# LPCB218_-_RS485_MUX_CONTROL.net
KiCad netlist of a schematic drawn in Altium Designer
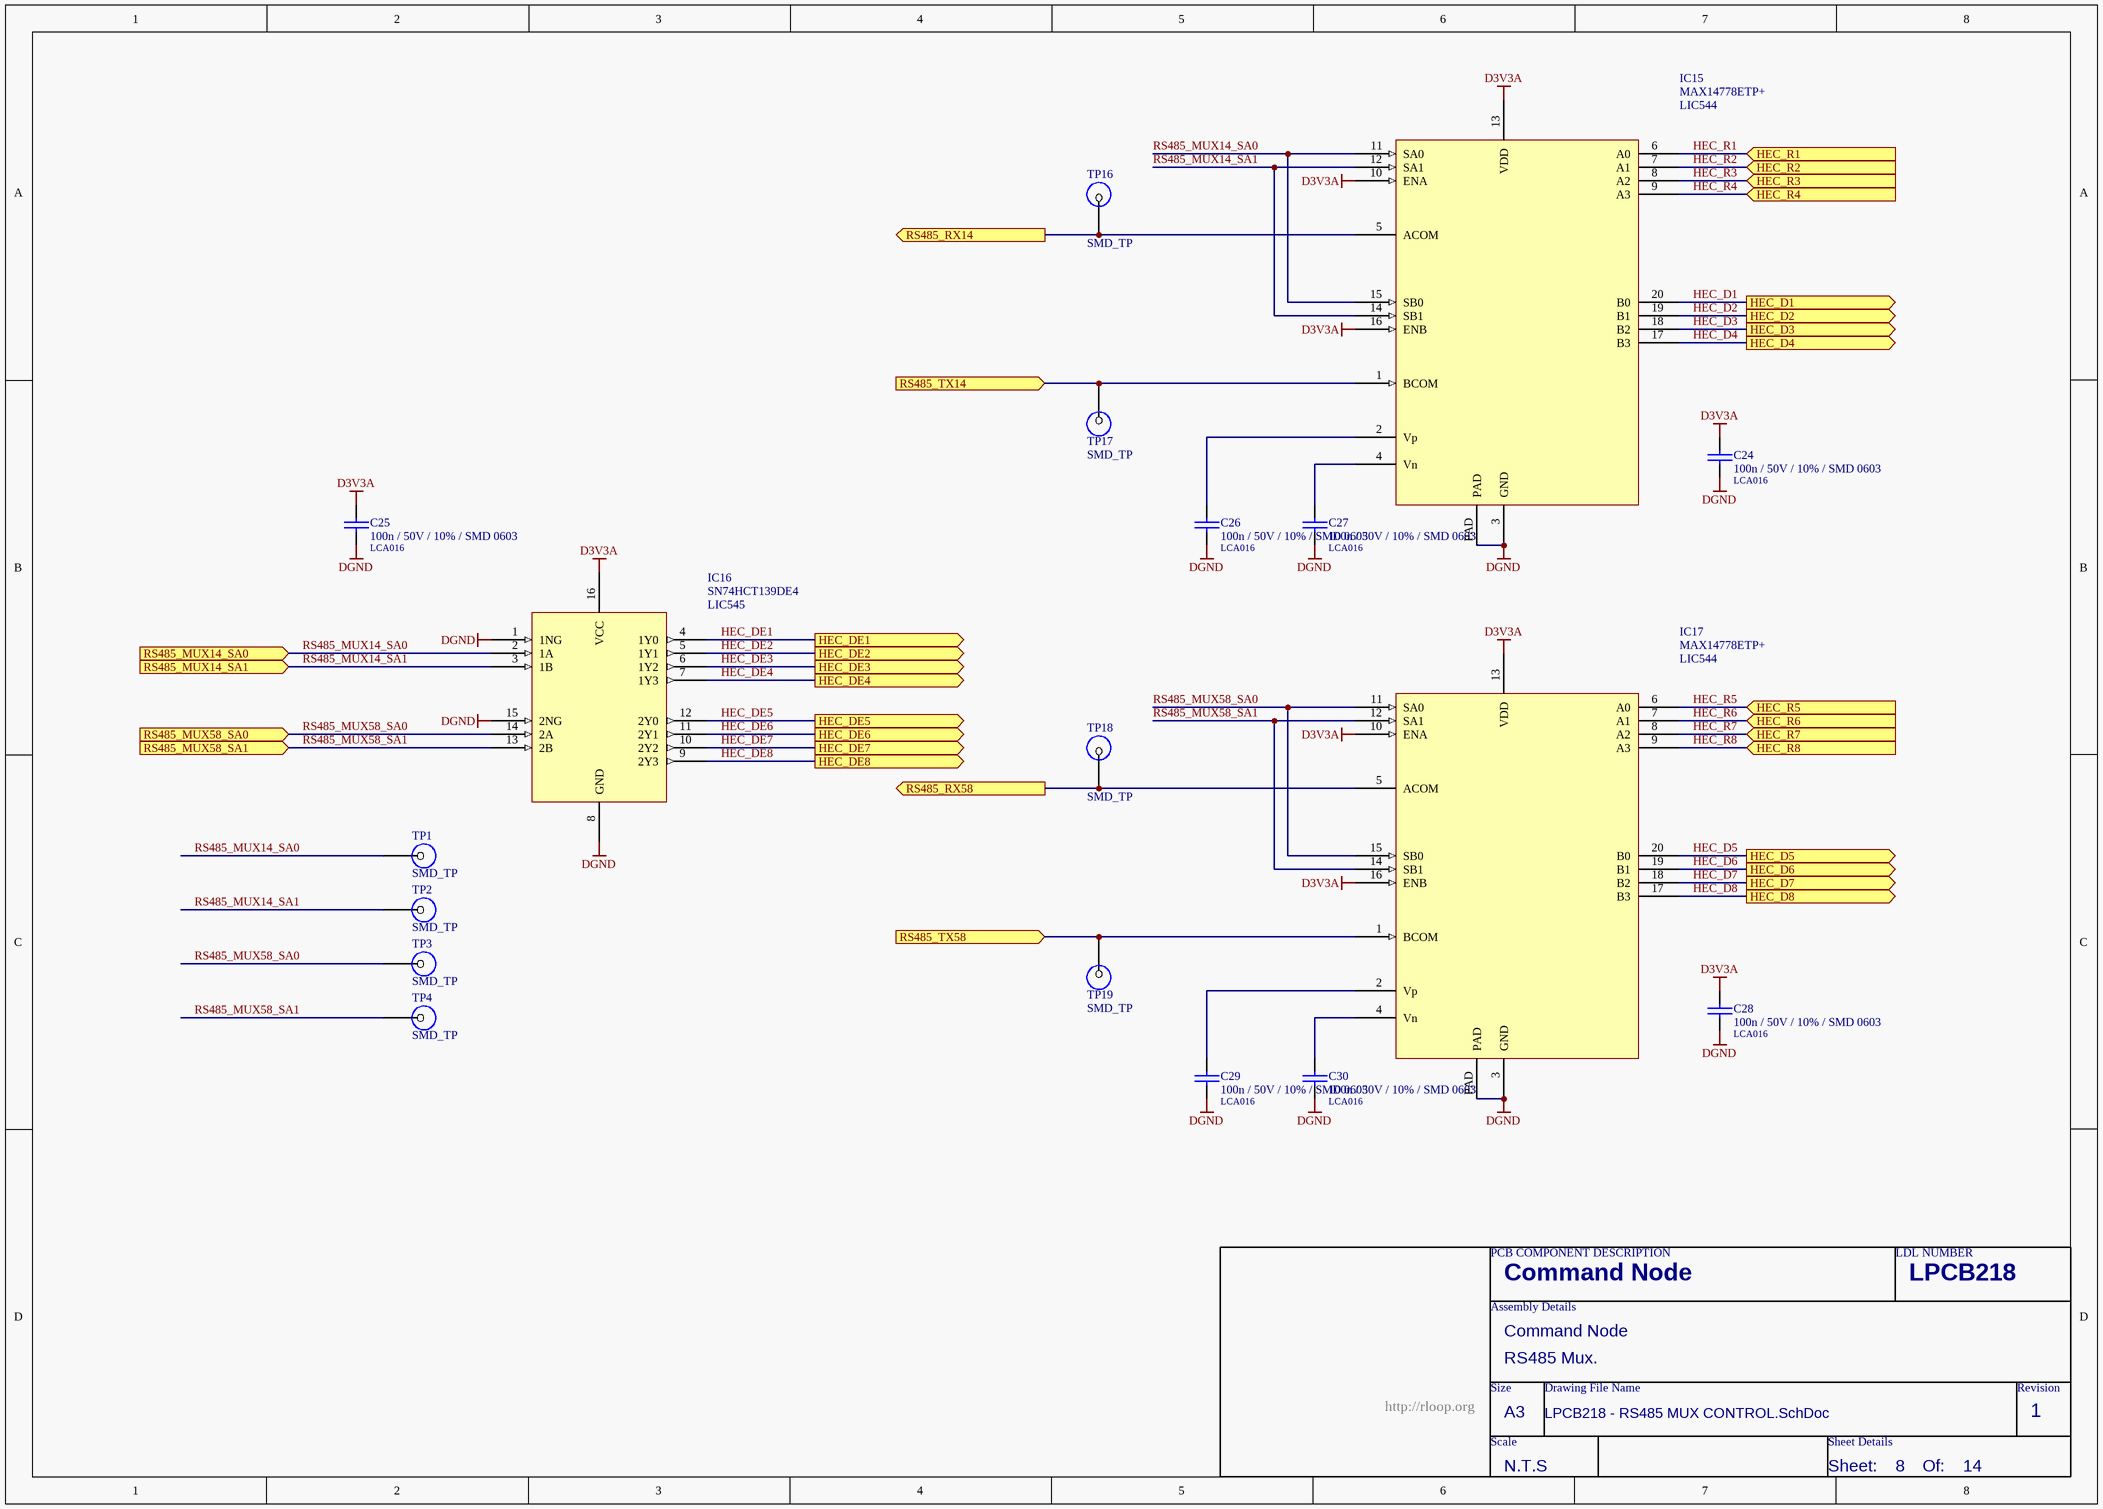
[diagram p0: LPCB218 - RS485 MUX CONTROL.SchDoc]

(export (version "E")
  (design (tool "Eeschema 10.0.6"))
  (components
    (comp (ref "C24")
      (value "100n / 50V / 10% / SMD 0603")
      (footprint "LFP011__CC1608-0603-IPC7351_B")
      (description "Capacitor, Ceramic Chip, 100nF (0.1uF), 50V, 5%, SMD 0603 [LCA016]")
      (fields (field (name "LDL_NUMBER") "LCA016"))
      (libsource (lib "LDL_Capacitors") (part "100n / 50V / 10% / SMD 0603"))
    )
    (comp (ref "C25")
      (value "100n / 50V / 10% / SMD 0603")
      (footprint "LFP011__CC1608-0603-IPC7351_B")
      (description "Capacitor, Ceramic Chip, 100nF (0.1uF), 50V, 5%, SMD 0603 [LCA016]")
      (fields (field (name "LDL_NUMBER") "LCA016"))
      (libsource (lib "LDL_Capacitors") (part "100n / 50V / 10% / SMD 0603"))
    )
    (comp (ref "C26")
      (value "100n / 50V / 10% / SMD 0603")
      (footprint "LFP011__CC1608-0603-IPC7351_B")
      (description "Capacitor, Ceramic Chip, 100nF (0.1uF), 50V, 5%, SMD 0603 [LCA016]")
      (fields (field (name "LDL_NUMBER") "LCA016"))
      (libsource (lib "LDL_Capacitors") (part "100n / 50V / 10% / SMD 0603"))
    )
    (comp (ref "C27")
      (value "100n / 50V / 10% / SMD 0603")
      (footprint "LFP011__CC1608-0603-IPC7351_B")
      (description "Capacitor, Ceramic Chip, 100nF (0.1uF), 50V, 5%, SMD 0603 [LCA016]")
      (fields (field (name "LDL_NUMBER") "LCA016"))
      (libsource (lib "LDL_Capacitors") (part "100n / 50V / 10% / SMD 0603"))
    )
    (comp (ref "C28")
      (value "100n / 50V / 10% / SMD 0603")
      (footprint "LFP011__CC1608-0603-IPC7351_B")
      (description "Capacitor, Ceramic Chip, 100nF (0.1uF), 50V, 5%, SMD 0603 [LCA016]")
      (fields (field (name "LDL_NUMBER") "LCA016"))
      (libsource (lib "LDL_Capacitors") (part "100n / 50V / 10% / SMD 0603"))
    )
    (comp (ref "C29")
      (value "100n / 50V / 10% / SMD 0603")
      (footprint "LFP011__CC1608-0603-IPC7351_B")
      (description "Capacitor, Ceramic Chip, 100nF (0.1uF), 50V, 5%, SMD 0603 [LCA016]")
      (fields (field (name "LDL_NUMBER") "LCA016"))
      (libsource (lib "LDL_Capacitors") (part "100n / 50V / 10% / SMD 0603"))
    )
    (comp (ref "C30")
      (value "100n / 50V / 10% / SMD 0603")
      (footprint "LFP011__CC1608-0603-IPC7351_B")
      (description "Capacitor, Ceramic Chip, 100nF (0.1uF), 50V, 5%, SMD 0603 [LCA016]")
      (fields (field (name "LDL_NUMBER") "LCA016"))
      (libsource (lib "LDL_Capacitors") (part "100n / 50V / 10% / SMD 0603"))
    )
    (comp (ref "IC15")
      (value "MAX14778ETP+")
      (footprint "LFP014__QFN65P500X500X80_HS-21N")
      (description "IC, Mux 25V, SMD QFN20 [LIC544]")
      (fields (field (name "LDL_NUMBER") "LIC544"))
      (libsource (lib "LDL_Semiconductors") (part "MAX14778ETP+"))
    )
    (comp (ref "IC16")
      (value "SN74HCT139DE4")
      (footprint "LFP079__SOP16")
      (description "IC, Dual 2-4 Demux, SMD SOIC-16")
      (fields (field (name "LDL_NUMBER") "LIC545"))
      (libsource (lib "LDL_Semiconductors") (part "SN74HCT139DE4"))
    )
    (comp (ref "IC17")
      (value "MAX14778ETP+")
      (footprint "LFP014__QFN65P500X500X80_HS-21N")
      (description "IC, Mux 25V, SMD QFN20 [LIC544]")
      (fields (field (name "LDL_NUMBER") "LIC544"))
      (libsource (lib "LDL_Semiconductors") (part "MAX14778ETP+"))
    )
    (comp (ref "TP1")
      (value "SMD_TP")
      (footprint "SMD-TP")
      (description "SMD Test Point")
      (libsource (lib "LDL_Connectors") (part "SMD_TP"))
    )
    (comp (ref "TP2")
      (value "SMD_TP")
      (footprint "SMD-TP")
      (description "SMD Test Point")
      (libsource (lib "LDL_Connectors") (part "SMD_TP"))
    )
    (comp (ref "TP3")
      (value "SMD_TP")
      (footprint "SMD-TP")
      (description "SMD Test Point")
      (libsource (lib "LDL_Connectors") (part "SMD_TP"))
    )
    (comp (ref "TP4")
      (value "SMD_TP")
      (footprint "SMD-TP")
      (description "SMD Test Point")
      (libsource (lib "LDL_Connectors") (part "SMD_TP"))
    )
    (comp (ref "TP16")
      (value "SMD_TP")
      (footprint "SMD-TP")
      (description "SMD Test Point")
      (libsource (lib "LDL_Connectors") (part "SMD_TP"))
    )
    (comp (ref "TP17")
      (value "SMD_TP")
      (footprint "SMD-TP")
      (description "SMD Test Point")
      (libsource (lib "LDL_Connectors") (part "SMD_TP"))
    )
    (comp (ref "TP18")
      (value "SMD_TP")
      (footprint "SMD-TP")
      (description "SMD Test Point")
      (libsource (lib "LDL_Connectors") (part "SMD_TP"))
    )
    (comp (ref "TP19")
      (value "SMD_TP")
      (footprint "SMD-TP")
      (description "SMD Test Point")
      (libsource (lib "LDL_Connectors") (part "SMD_TP"))
    )
  )
  (nets
    (net (code "1") (name "/HEC_D1") (class "Default")
      (node (ref "IC15") (pin "20") (pinfunction "B0_20") (pintype "passive"))
    )
    (net (code "2") (name "/HEC_D2") (class "Default")
      (node (ref "IC15") (pin "19") (pinfunction "B1_19") (pintype "passive"))
    )
    (net (code "3") (name "/HEC_D3") (class "Default")
      (node (ref "IC15") (pin "18") (pinfunction "B2_18") (pintype "passive"))
    )
    (net (code "4") (name "/HEC_D4") (class "Default")
      (node (ref "IC15") (pin "17") (pinfunction "B3_17") (pintype "passive"))
    )
    (net (code "5") (name "/HEC_D5") (class "Default")
      (node (ref "IC17") (pin "20") (pinfunction "B0_20") (pintype "passive"))
    )
    (net (code "6") (name "/HEC_D6") (class "Default")
      (node (ref "IC17") (pin "19") (pinfunction "B1_19") (pintype "passive"))
    )
    (net (code "7") (name "/HEC_D7") (class "Default")
      (node (ref "IC17") (pin "18") (pinfunction "B2_18") (pintype "passive"))
    )
    (net (code "8") (name "/HEC_D8") (class "Default")
      (node (ref "IC17") (pin "17") (pinfunction "B3_17") (pintype "passive"))
    )
    (net (code "9") (name "/HEC_DE1") (class "Default")
      (node (ref "IC16") (pin "4") (pinfunction "1Y0_4") (pintype "output"))
    )
    (net (code "10") (name "/HEC_DE2") (class "Default")
      (node (ref "IC16") (pin "5") (pinfunction "1Y1_5") (pintype "output"))
    )
    (net (code "11") (name "/HEC_DE3") (class "Default")
      (node (ref "IC16") (pin "6") (pinfunction "1Y2_6") (pintype "output"))
    )
    (net (code "12") (name "/HEC_DE4") (class "Default")
      (node (ref "IC16") (pin "7") (pinfunction "1Y3_7") (pintype "output"))
    )
    (net (code "13") (name "/HEC_DE5") (class "Default")
      (node (ref "IC16") (pin "12") (pinfunction "2Y0_12") (pintype "output"))
    )
    (net (code "14") (name "/HEC_DE6") (class "Default")
      (node (ref "IC16") (pin "11") (pinfunction "2Y1_11") (pintype "output"))
    )
    (net (code "15") (name "/HEC_DE7") (class "Default")
      (node (ref "IC16") (pin "10") (pinfunction "2Y2_10") (pintype "output"))
    )
    (net (code "16") (name "/HEC_DE8") (class "Default")
      (node (ref "IC16") (pin "9") (pinfunction "2Y3_9") (pintype "output"))
    )
    (net (code "17") (name "/HEC_R1") (class "Default")
      (node (ref "IC15") (pin "6") (pinfunction "A0_6") (pintype "passive"))
    )
    (net (code "18") (name "/HEC_R2") (class "Default")
      (node (ref "IC15") (pin "7") (pinfunction "A1_7") (pintype "passive"))
    )
    (net (code "19") (name "/HEC_R3") (class "Default")
      (node (ref "IC15") (pin "8") (pinfunction "A2_8") (pintype "passive"))
    )
    (net (code "20") (name "/HEC_R4") (class "Default")
      (node (ref "IC15") (pin "9") (pinfunction "A3_9") (pintype "passive"))
    )
    (net (code "21") (name "/HEC_R5") (class "Default")
      (node (ref "IC17") (pin "6") (pinfunction "A0_6") (pintype "passive"))
    )
    (net (code "22") (name "/HEC_R6") (class "Default")
      (node (ref "IC17") (pin "7") (pinfunction "A1_7") (pintype "passive"))
    )
    (net (code "23") (name "/HEC_R7") (class "Default")
      (node (ref "IC17") (pin "8") (pinfunction "A2_8") (pintype "passive"))
    )
    (net (code "24") (name "/HEC_R8") (class "Default")
      (node (ref "IC17") (pin "9") (pinfunction "A3_9") (pintype "passive"))
    )
    (net (code "25") (name "/RS485_MUX14_SA0") (class "Default")
      (node (ref "IC15") (pin "11") (pinfunction "SA0_11") (pintype "input"))
      (node (ref "IC15") (pin "15") (pinfunction "SB0_15") (pintype "input"))
      (node (ref "IC16") (pin "2") (pinfunction "1A_2") (pintype "input"))
      (node (ref "TP1") (pin "1") (pintype "passive"))
    )
    (net (code "26") (name "/RS485_MUX14_SA1") (class "Default")
      (node (ref "IC15") (pin "12") (pinfunction "SA1_12") (pintype "input"))
      (node (ref "IC15") (pin "14") (pinfunction "SB1_14") (pintype "input"))
      (node (ref "IC16") (pin "3") (pinfunction "1B_3") (pintype "input"))
      (node (ref "TP2") (pin "1") (pintype "passive"))
    )
    (net (code "27") (name "/RS485_MUX58_SA0") (class "Default")
      (node (ref "IC16") (pin "14") (pinfunction "2A_14") (pintype "input"))
      (node (ref "IC17") (pin "11") (pinfunction "SA0_11") (pintype "input"))
      (node (ref "IC17") (pin "15") (pinfunction "SB0_15") (pintype "input"))
      (node (ref "TP3") (pin "1") (pintype "passive"))
    )
    (net (code "28") (name "/RS485_MUX58_SA1") (class "Default")
      (node (ref "IC16") (pin "13") (pinfunction "2B_13") (pintype "input"))
      (node (ref "IC17") (pin "12") (pinfunction "SA1_12") (pintype "input"))
      (node (ref "IC17") (pin "14") (pinfunction "SB1_14") (pintype "input"))
      (node (ref "TP4") (pin "1") (pintype "passive"))
    )
    (net (code "29") (name "/RS485_RX14") (class "Default")
      (node (ref "IC15") (pin "5") (pinfunction "ACOM_5") (pintype "passive"))
      (node (ref "TP16") (pin "1") (pintype "passive"))
    )
    (net (code "30") (name "/RS485_RX58") (class "Default")
      (node (ref "IC17") (pin "5") (pinfunction "ACOM_5") (pintype "passive"))
      (node (ref "TP18") (pin "1") (pintype "passive"))
    )
    (net (code "31") (name "/RS485_TX14") (class "Default")
      (node (ref "IC15") (pin "1") (pinfunction "BCOM_1") (pintype "input"))
      (node (ref "TP17") (pin "1") (pintype "passive"))
    )
    (net (code "32") (name "/RS485_TX58") (class "Default")
      (node (ref "IC17") (pin "1") (pinfunction "BCOM_1") (pintype "input"))
      (node (ref "TP19") (pin "1") (pintype "passive"))
    )
    (net (code "33") (name "D3V3A") (class "Default")
      (node (ref "C24") (pin "1") (pintype "passive"))
      (node (ref "C25") (pin "1") (pintype "passive"))
      (node (ref "C28") (pin "1") (pintype "passive"))
      (node (ref "IC15") (pin "10") (pinfunction "ENA_10") (pintype "input"))
      (node (ref "IC15") (pin "13") (pinfunction "VDD_13") (pintype "power_in"))
      (node (ref "IC15") (pin "16") (pinfunction "ENB_16") (pintype "input"))
      (node (ref "IC16") (pin "16") (pinfunction "VCC_16") (pintype "power_in"))
      (node (ref "IC17") (pin "10") (pinfunction "ENA_10") (pintype "input"))
      (node (ref "IC17") (pin "13") (pinfunction "VDD_13") (pintype "power_in"))
      (node (ref "IC17") (pin "16") (pinfunction "ENB_16") (pintype "input"))
    )
    (net (code "34") (name "DGND") (class "Default")
      (node (ref "C24") (pin "2") (pintype "passive"))
      (node (ref "C25") (pin "2") (pintype "passive"))
      (node (ref "C26") (pin "2") (pintype "passive"))
      (node (ref "C27") (pin "2") (pintype "passive"))
      (node (ref "C28") (pin "2") (pintype "passive"))
      (node (ref "C29") (pin "2") (pintype "passive"))
      (node (ref "C30") (pin "2") (pintype "passive"))
      (node (ref "IC15") (pin "3") (pinfunction "GND_3") (pintype "power_in"))
      (node (ref "IC15") (pin "PAD") (pinfunction "PAD_PAD") (pintype "power_in"))
      (node (ref "IC16") (pin "1") (pinfunction "1NG_1") (pintype "input"))
      (node (ref "IC16") (pin "15") (pinfunction "2NG_15") (pintype "input"))
      (node (ref "IC16") (pin "8") (pinfunction "GND_8") (pintype "power_in"))
      (node (ref "IC17") (pin "3") (pinfunction "GND_3") (pintype "power_in"))
      (node (ref "IC17") (pin "PAD") (pinfunction "PAD_PAD") (pintype "power_in"))
    )
    (net (code "35") (name "Net-(IC15-Vn)") (class "Default")
      (node (ref "C27") (pin "1") (pintype "passive"))
      (node (ref "IC15") (pin "4") (pinfunction "Vn_4") (pintype "passive"))
    )
    (net (code "36") (name "Net-(IC15-Vp)") (class "Default")
      (node (ref "C26") (pin "1") (pintype "passive"))
      (node (ref "IC15") (pin "2") (pinfunction "Vp_2") (pintype "passive"))
    )
    (net (code "37") (name "Net-(IC17-Vn)") (class "Default")
      (node (ref "C30") (pin "1") (pintype "passive"))
      (node (ref "IC17") (pin "4") (pinfunction "Vn_4") (pintype "passive"))
    )
    (net (code "38") (name "Net-(IC17-Vp)") (class "Default")
      (node (ref "C29") (pin "1") (pintype "passive"))
      (node (ref "IC17") (pin "2") (pinfunction "Vp_2") (pintype "passive"))
    )
  )
)
